# HeadAmp1_trace1.net
KiCad netlist of a schematic drawn in EAGLE
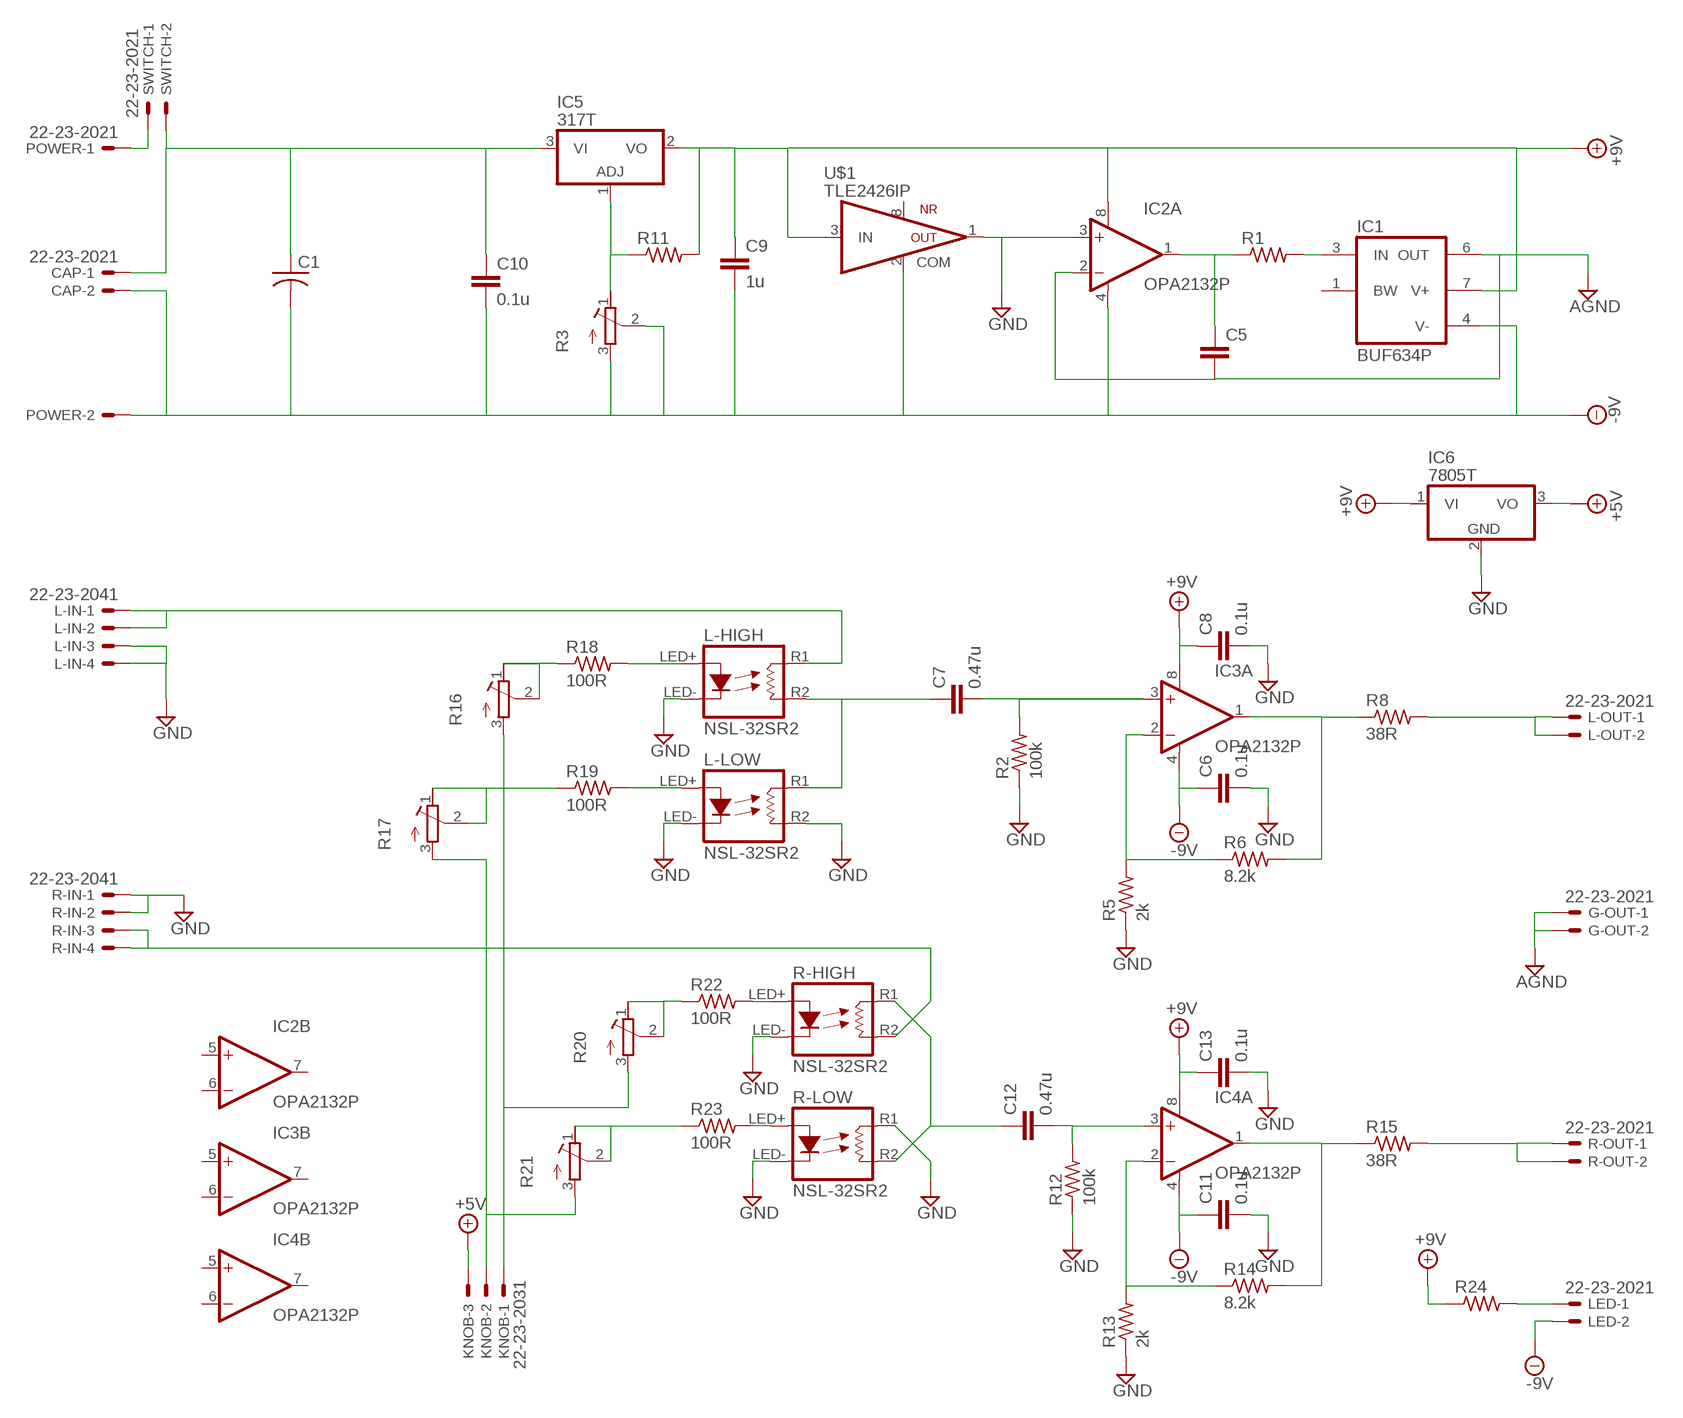
[diagram p0: schematic, sheet 1]

(export (version "E")
  (design (tool "Eeschema 10.0.6"))
  (components
    (comp (ref "C1")
      (value "C-US050-075X075")
      (footprint "eagle-import:C050-075X075")
      (libsource (lib "eagle-import") (part "C-US050-075X075"))
    )
    (comp (ref "C5")
      (value "C5/3")
      (footprint "eagle-import:C5B3")
      (libsource (lib "eagle-import") (part "C5/3"))
    )
    (comp (ref "C6")
      (value "0.1u")
      (footprint "eagle-import:C5B3")
      (libsource (lib "eagle-import") (part "C5/3"))
    )
    (comp (ref "C7")
      (value "0.47u")
      (footprint "eagle-import:C5B3")
      (libsource (lib "eagle-import") (part "C5/3"))
    )
    (comp (ref "C8")
      (value "0.1u")
      (footprint "eagle-import:C5B3")
      (libsource (lib "eagle-import") (part "C5/3"))
    )
    (comp (ref "C9")
      (value "1u")
      (footprint "eagle-import:C5B3")
      (libsource (lib "eagle-import") (part "C5/3"))
    )
    (comp (ref "C10")
      (value "0.1u")
      (footprint "eagle-import:C5B3")
      (libsource (lib "eagle-import") (part "C5/3"))
    )
    (comp (ref "C11")
      (value "0.1u")
      (footprint "eagle-import:C5B3")
      (libsource (lib "eagle-import") (part "C5/3"))
    )
    (comp (ref "C12")
      (value "0.47u")
      (footprint "eagle-import:C5B3")
      (libsource (lib "eagle-import") (part "C5/3"))
    )
    (comp (ref "C13")
      (value "0.1u")
      (footprint "eagle-import:C5B3")
      (libsource (lib "eagle-import") (part "C5/3"))
    )
    (comp (ref "CAP")
      (value "22-23-2021")
      (footprint "eagle-import:22-23-2021")
      (fields (field (name "MF") "MOLEX"))
      (libsource (lib "eagle-import") (part "22-23-2021"))
    )
    (comp (ref "G-OUT")
      (value "22-23-2021")
      (footprint "eagle-import:22-23-2021")
      (fields (field (name "MF") "MOLEX"))
      (libsource (lib "eagle-import") (part "22-23-2021"))
    )
    (comp (ref "IC1")
      (value "BUF634P")
      (footprint "eagle-import:DIL08")
      (fields (field (name "MF") "TEXAS INSTRUMENTS"))
      (libsource (lib "eagle-import") (part "BUF634P"))
    )
    (comp (ref "IC2")
      (value "OPA2132P")
      (footprint "eagle-import:DIL08")
      (libsource (lib "eagle-import") (part "OPA2132P"))
    )
    (comp (ref "IC3")
      (value "OPA2132P")
      (footprint "eagle-import:DIL08")
      (libsource (lib "eagle-import") (part "OPA2132P"))
    )
    (comp (ref "IC4")
      (value "OPA2132P")
      (footprint "eagle-import:DIL08")
      (libsource (lib "eagle-import") (part "OPA2132P"))
    )
    (comp (ref "IC5")
      (value "317T")
      (footprint "eagle-import:TO220H")
      (libsource (lib "eagle-import") (part "317T"))
    )
    (comp (ref "IC6")
      (value "7805T")
      (footprint "eagle-import:TO220H")
      (libsource (lib "eagle-import") (part "78T05"))
    )
    (comp (ref "KNOB")
      (value "22-23-2031")
      (footprint "eagle-import:22-23-2031")
      (fields (field (name "MF") "MOLEX"))
      (libsource (lib "eagle-import") (part "22-23-2031"))
    )
    (comp (ref "L-HIGH")
      (value "NSL-32SR2")
      (footprint "eagle-import:OPTO_32SR")
      (libsource (lib "eagle-import") (part "NSL-32SR2"))
    )
    (comp (ref "L-IN")
      (value "22-23-2041")
      (footprint "eagle-import:22-23-2041")
      (fields (field (name "MF") "MOLEX"))
      (libsource (lib "eagle-import") (part "22-23-2041"))
    )
    (comp (ref "L-LOW")
      (value "NSL-32SR2")
      (footprint "eagle-import:OPTO_32SR")
      (libsource (lib "eagle-import") (part "NSL-32SR2"))
    )
    (comp (ref "L-OUT")
      (value "22-23-2021")
      (footprint "eagle-import:22-23-2021")
      (fields (field (name "MF") "MOLEX"))
      (libsource (lib "eagle-import") (part "22-23-2021"))
    )
    (comp (ref "LED")
      (value "22-23-2021")
      (footprint "eagle-import:22-23-2021")
      (fields (field (name "MF") "MOLEX"))
      (libsource (lib "eagle-import") (part "22-23-2021"))
    )
    (comp (ref "POWER")
      (value "22-23-2021")
      (footprint "eagle-import:22-23-2021")
      (fields (field (name "MF") "MOLEX"))
      (libsource (lib "eagle-import") (part "22-23-2021"))
    )
    (comp (ref "R-HIGH")
      (value "NSL-32SR2")
      (footprint "eagle-import:OPTO_32SR")
      (libsource (lib "eagle-import") (part "NSL-32SR2"))
    )
    (comp (ref "R-IN")
      (value "22-23-2041")
      (footprint "eagle-import:22-23-2041")
      (fields (field (name "MF") "MOLEX"))
      (libsource (lib "eagle-import") (part "22-23-2041"))
    )
    (comp (ref "R-LOW")
      (value "NSL-32SR2")
      (footprint "eagle-import:OPTO_32SR")
      (libsource (lib "eagle-import") (part "NSL-32SR2"))
    )
    (comp (ref "R-OUT")
      (value "22-23-2021")
      (footprint "eagle-import:22-23-2021")
      (fields (field (name "MF") "MOLEX"))
      (libsource (lib "eagle-import") (part "22-23-2021"))
    )
    (comp (ref "R1")
      (value "R-US_0207/10")
      (footprint "eagle-import:0207_10")
      (libsource (lib "eagle-import") (part "R-US_0207/10"))
    )
    (comp (ref "R2")
      (value "100k")
      (footprint "eagle-import:0207_10")
      (libsource (lib "eagle-import") (part "R-US_0207/10"))
    )
    (comp (ref "R3")
      (value "R-TRIMMT93YB")
      (footprint "eagle-import:RTRIMT93YB")
      (libsource (lib "eagle-import") (part "R-TRIMMT93YB"))
    )
    (comp (ref "R5")
      (value "2k")
      (footprint "eagle-import:0207_10")
      (libsource (lib "eagle-import") (part "R-US_0207/10"))
    )
    (comp (ref "R6")
      (value "8.2k")
      (footprint "eagle-import:0207_10")
      (libsource (lib "eagle-import") (part "R-US_0207/10"))
    )
    (comp (ref "R8")
      (value "38R")
      (footprint "eagle-import:0207_10")
      (libsource (lib "eagle-import") (part "R-US_0207/10"))
    )
    (comp (ref "R11")
      (value "R-US_0207/10")
      (footprint "eagle-import:0207_10")
      (libsource (lib "eagle-import") (part "R-US_0207/10"))
    )
    (comp (ref "R12")
      (value "100k")
      (footprint "eagle-import:0207_10")
      (libsource (lib "eagle-import") (part "R-US_0207/10"))
    )
    (comp (ref "R13")
      (value "2k")
      (footprint "eagle-import:0207_10")
      (libsource (lib "eagle-import") (part "R-US_0207/10"))
    )
    (comp (ref "R14")
      (value "8.2k")
      (footprint "eagle-import:0207_10")
      (libsource (lib "eagle-import") (part "R-US_0207/10"))
    )
    (comp (ref "R15")
      (value "38R")
      (footprint "eagle-import:0207_10")
      (libsource (lib "eagle-import") (part "R-US_0207/10"))
    )
    (comp (ref "R16")
      (value "R-TRIMMT93YB")
      (footprint "eagle-import:RTRIMT93YB")
      (libsource (lib "eagle-import") (part "R-TRIMMT93YB"))
    )
    (comp (ref "R17")
      (value "R-TRIMMT93YB")
      (footprint "eagle-import:RTRIMT93YB")
      (libsource (lib "eagle-import") (part "R-TRIMMT93YB"))
    )
    (comp (ref "R18")
      (value "100R")
      (footprint "eagle-import:0207_10")
      (libsource (lib "eagle-import") (part "R-US_0207/10"))
    )
    (comp (ref "R19")
      (value "100R")
      (footprint "eagle-import:0207_10")
      (libsource (lib "eagle-import") (part "R-US_0207/10"))
    )
    (comp (ref "R20")
      (value "R-TRIMMT93YB")
      (footprint "eagle-import:RTRIMT93YB")
      (libsource (lib "eagle-import") (part "R-TRIMMT93YB"))
    )
    (comp (ref "R21")
      (value "R-TRIMMT93YB")
      (footprint "eagle-import:RTRIMT93YB")
      (libsource (lib "eagle-import") (part "R-TRIMMT93YB"))
    )
    (comp (ref "R22")
      (value "100R")
      (footprint "eagle-import:0207_10")
      (libsource (lib "eagle-import") (part "R-US_0207/10"))
    )
    (comp (ref "R23")
      (value "100R")
      (footprint "eagle-import:0207_10")
      (libsource (lib "eagle-import") (part "R-US_0207/10"))
    )
    (comp (ref "R24")
      (value "R-US_0207/10")
      (footprint "eagle-import:0207_10")
      (libsource (lib "eagle-import") (part "R-US_0207/10"))
    )
    (comp (ref "SWITCH")
      (value "22-23-2021")
      (footprint "eagle-import:22-23-2021")
      (fields (field (name "MF") "MOLEX"))
      (libsource (lib "eagle-import") (part "22-23-2021"))
    )
    (comp (ref "U$1")
      (value "TLE2426IP")
      (footprint "eagle-import:DIL08")
      (libsource (lib "eagle-import") (part "TLE2426IP"))
    )
  )
  (nets
    (net (code "1") (name "+5V") (class "Default")
      (node (ref "IC6") (pin "3") (pinfunction "VO_3") (pintype "passive"))
      (node (ref "KNOB") (pin "3") (pinfunction "S_3") (pintype "passive"))
    )
    (net (code "2") (name "+9V") (class "Default")
      (node (ref "C13") (pin "1") (pinfunction "1_1") (pintype "passive"))
      (node (ref "C8") (pin "1") (pinfunction "1_1") (pintype "passive"))
      (node (ref "C9") (pin "1") (pinfunction "1_1") (pintype "passive"))
      (node (ref "IC1") (pin "7") (pinfunction "V+_7") (pintype "power_in"))
      (node (ref "IC2") (pin "8") (pinfunction "V+_8") (pintype "power_in"))
      (node (ref "IC3") (pin "8") (pinfunction "V+_8") (pintype "power_in"))
      (node (ref "IC4") (pin "8") (pinfunction "V+_8") (pintype "power_in"))
      (node (ref "IC5") (pin "2") (pinfunction "VO_2") (pintype "passive"))
      (node (ref "IC6") (pin "1") (pinfunction "VI_1") (pintype "input"))
      (node (ref "R11") (pin "2") (pinfunction "2_2") (pintype "passive"))
      (node (ref "R24") (pin "1") (pinfunction "1_1") (pintype "passive"))
      (node (ref "U$1") (pin "3") (pinfunction "IN_3") (pintype "input"))
    )
    (net (code "3") (name "-9V") (class "Default")
      (node (ref "C1") (pin "2") (pinfunction "2_2") (pintype "passive"))
      (node (ref "C10") (pin "2") (pinfunction "2_2") (pintype "passive"))
      (node (ref "C11") (pin "1") (pinfunction "1_1") (pintype "passive"))
      (node (ref "C6") (pin "1") (pinfunction "1_1") (pintype "passive"))
      (node (ref "C9") (pin "2") (pinfunction "2_2") (pintype "passive"))
      (node (ref "CAP") (pin "2") (pinfunction "S_2") (pintype "passive"))
      (node (ref "IC1") (pin "4") (pinfunction "V-_4") (pintype "power_in"))
      (node (ref "IC2") (pin "4") (pinfunction "V-_4") (pintype "power_in"))
      (node (ref "IC3") (pin "4") (pinfunction "V-_4") (pintype "power_in"))
      (node (ref "IC4") (pin "4") (pinfunction "V-_4") (pintype "power_in"))
      (node (ref "LED") (pin "2") (pinfunction "S_2") (pintype "passive"))
      (node (ref "POWER") (pin "2") (pinfunction "S_2") (pintype "passive"))
      (node (ref "R3") (pin "2") (pinfunction "S_2") (pintype "passive"))
      (node (ref "R3") (pin "3") (pinfunction "E_3") (pintype "passive"))
      (node (ref "U$1") (pin "2") (pinfunction "COMMON_2") (pintype "passive"))
    )
    (net (code "4") (name "AGND") (class "Default")
      (node (ref "C5") (pin "2") (pinfunction "2_2") (pintype "passive"))
      (node (ref "G-OUT") (pin "1") (pinfunction "S_1") (pintype "passive"))
      (node (ref "G-OUT") (pin "2") (pinfunction "S_2") (pintype "passive"))
      (node (ref "IC1") (pin "6") (pinfunction "OUT_6") (pintype "output"))
      (node (ref "IC2") (pin "2") (pinfunction "-IN_2") (pintype "input"))
    )
    (net (code "5") (name "GND") (class "Default")
      (node (ref "C11") (pin "2") (pinfunction "2_2") (pintype "passive"))
      (node (ref "C13") (pin "2") (pinfunction "2_2") (pintype "passive"))
      (node (ref "C6") (pin "2") (pinfunction "2_2") (pintype "passive"))
      (node (ref "C8") (pin "2") (pinfunction "2_2") (pintype "passive"))
      (node (ref "IC2") (pin "3") (pinfunction "+IN_3") (pintype "input"))
      (node (ref "IC6") (pin "2") (pinfunction "GND_2") (pintype "passive"))
      (node (ref "L-HIGH") (pin "LED-") (pinfunction "C_LED-") (pintype "passive"))
      (node (ref "L-IN") (pin "3") (pinfunction "S_3") (pintype "passive"))
      (node (ref "L-IN") (pin "4") (pinfunction "S_4") (pintype "passive"))
      (node (ref "L-LOW") (pin "LED-") (pinfunction "C_LED-") (pintype "passive"))
      (node (ref "L-LOW") (pin "R2") (pinfunction "L2_R2") (pintype "passive"))
      (node (ref "R-HIGH") (pin "LED-") (pinfunction "C_LED-") (pintype "passive"))
      (node (ref "R-IN") (pin "1") (pinfunction "S_1") (pintype "passive"))
      (node (ref "R-IN") (pin "2") (pinfunction "S_2") (pintype "passive"))
      (node (ref "R-LOW") (pin "LED-") (pinfunction "C_LED-") (pintype "passive"))
      (node (ref "R-LOW") (pin "R1") (pinfunction "L1_R1") (pintype "passive"))
      (node (ref "R12") (pin "1") (pinfunction "1_1") (pintype "passive"))
      (node (ref "R13") (pin "1") (pinfunction "1_1") (pintype "passive"))
      (node (ref "R2") (pin "1") (pinfunction "1_1") (pintype "passive"))
      (node (ref "R5") (pin "1") (pinfunction "1_1") (pintype "passive"))
      (node (ref "U$1") (pin "1") (pinfunction "OUT_1") (pintype "passive"))
    )
    (net (code "6") (name "Net-(CAPA-S)") (class "Default")
      (node (ref "C1") (pin "1") (pinfunction "1_1") (pintype "passive"))
      (node (ref "C10") (pin "1") (pinfunction "1_1") (pintype "passive"))
      (node (ref "CAP") (pin "1") (pinfunction "S_1") (pintype "passive"))
      (node (ref "IC5") (pin "3") (pinfunction "VI_3") (pintype "input"))
      (node (ref "SWITCH") (pin "2") (pinfunction "S_2") (pintype "passive"))
    )
    (net (code "7") (name "Net-(IC1-IN)") (class "Default")
      (node (ref "IC1") (pin "3") (pinfunction "IN_3") (pintype "input"))
      (node (ref "R1") (pin "2") (pinfunction "2_2") (pintype "passive"))
    )
    (net (code "8") (name "Net-(IC2A-OUT)") (class "Default")
      (node (ref "C5") (pin "1") (pinfunction "1_1") (pintype "passive"))
      (node (ref "IC2") (pin "1") (pinfunction "OUT_1") (pintype "output"))
      (node (ref "R1") (pin "1") (pinfunction "1_1") (pintype "passive"))
    )
    (net (code "9") (name "Net-(IC3A-+IN)") (class "Default")
      (node (ref "C7") (pin "2") (pinfunction "2_2") (pintype "passive"))
      (node (ref "IC3") (pin "3") (pinfunction "+IN_3") (pintype "input"))
      (node (ref "R2") (pin "2") (pinfunction "2_2") (pintype "passive"))
    )
    (net (code "10") (name "Net-(IC3A--IN)") (class "Default")
      (node (ref "IC3") (pin "2") (pinfunction "-IN_2") (pintype "input"))
      (node (ref "R5") (pin "2") (pinfunction "2_2") (pintype "passive"))
      (node (ref "R6") (pin "1") (pinfunction "1_1") (pintype "passive"))
    )
    (net (code "11") (name "Net-(IC3A-OUT)") (class "Default")
      (node (ref "IC3") (pin "1") (pinfunction "OUT_1") (pintype "output"))
      (node (ref "R6") (pin "2") (pinfunction "2_2") (pintype "passive"))
      (node (ref "R8") (pin "1") (pinfunction "1_1") (pintype "passive"))
    )
    (net (code "12") (name "Net-(IC4A-+IN)") (class "Default")
      (node (ref "C12") (pin "2") (pinfunction "2_2") (pintype "passive"))
      (node (ref "IC4") (pin "3") (pinfunction "+IN_3") (pintype "input"))
      (node (ref "R12") (pin "2") (pinfunction "2_2") (pintype "passive"))
    )
    (net (code "13") (name "Net-(IC4A--IN)") (class "Default")
      (node (ref "IC4") (pin "2") (pinfunction "-IN_2") (pintype "input"))
      (node (ref "R13") (pin "2") (pinfunction "2_2") (pintype "passive"))
      (node (ref "R14") (pin "1") (pinfunction "1_1") (pintype "passive"))
    )
    (net (code "14") (name "Net-(IC4A-OUT)") (class "Default")
      (node (ref "IC4") (pin "1") (pinfunction "OUT_1") (pintype "output"))
      (node (ref "R14") (pin "2") (pinfunction "2_2") (pintype "passive"))
      (node (ref "R15") (pin "1") (pinfunction "1_1") (pintype "passive"))
    )
    (net (code "15") (name "Net-(IC5-ADJ)") (class "Default")
      (node (ref "IC5") (pin "1") (pinfunction "ADJ_1") (pintype "input"))
      (node (ref "R11") (pin "1") (pinfunction "1_1") (pintype "passive"))
      (node (ref "R3") (pin "1") (pinfunction "A_1") (pintype "passive"))
    )
    (net (code "16") (name "Net-(KNOBA-S)") (class "Default")
      (node (ref "KNOB") (pin "1") (pinfunction "S_1") (pintype "passive"))
      (node (ref "R16") (pin "3") (pinfunction "E_3") (pintype "passive"))
      (node (ref "R20") (pin "3") (pinfunction "E_3") (pintype "passive"))
    )
    (net (code "17") (name "Net-(KNOBB-S)") (class "Default")
      (node (ref "KNOB") (pin "2") (pinfunction "S_2") (pintype "passive"))
      (node (ref "R17") (pin "3") (pinfunction "E_3") (pintype "passive"))
      (node (ref "R21") (pin "3") (pinfunction "E_3") (pintype "passive"))
    )
    (net (code "18") (name "Net-(L-HIGH-A)") (class "Default")
      (node (ref "L-HIGH") (pin "LED+") (pinfunction "A_LED+") (pintype "passive"))
      (node (ref "R18") (pin "2") (pinfunction "2_2") (pintype "passive"))
    )
    (net (code "19") (name "Net-(L-HIGH-L1)") (class "Default")
      (node (ref "L-HIGH") (pin "R1") (pinfunction "L1_R1") (pintype "passive"))
      (node (ref "L-IN") (pin "1") (pinfunction "S_1") (pintype "passive"))
      (node (ref "L-IN") (pin "2") (pinfunction "S_2") (pintype "passive"))
    )
    (net (code "20") (name "Net-(L-HIGH-L2)") (class "Default")
      (node (ref "C7") (pin "1") (pinfunction "1_1") (pintype "passive"))
      (node (ref "L-HIGH") (pin "R2") (pinfunction "L2_R2") (pintype "passive"))
      (node (ref "L-LOW") (pin "R1") (pinfunction "L1_R1") (pintype "passive"))
    )
    (net (code "21") (name "Net-(L-LOW-A)") (class "Default")
      (node (ref "L-LOW") (pin "LED+") (pinfunction "A_LED+") (pintype "passive"))
      (node (ref "R19") (pin "2") (pinfunction "2_2") (pintype "passive"))
    )
    (net (code "22") (name "Net-(L-OUTA-S)") (class "Default")
      (node (ref "L-OUT") (pin "1") (pinfunction "S_1") (pintype "passive"))
      (node (ref "L-OUT") (pin "2") (pinfunction "S_2") (pintype "passive"))
      (node (ref "R8") (pin "2") (pinfunction "2_2") (pintype "passive"))
    )
    (net (code "23") (name "Net-(LEDA-S)") (class "Default")
      (node (ref "LED") (pin "1") (pinfunction "S_1") (pintype "passive"))
      (node (ref "R24") (pin "2") (pinfunction "2_2") (pintype "passive"))
    )
    (net (code "24") (name "Net-(POWERA-S)") (class "Default")
      (node (ref "POWER") (pin "1") (pinfunction "S_1") (pintype "passive"))
      (node (ref "SWITCH") (pin "1") (pinfunction "S_1") (pintype "passive"))
    )
    (net (code "25") (name "Net-(R-HIGH-A)") (class "Default")
      (node (ref "R-HIGH") (pin "LED+") (pinfunction "A_LED+") (pintype "passive"))
      (node (ref "R22") (pin "2") (pinfunction "2_2") (pintype "passive"))
    )
    (net (code "26") (name "Net-(R-HIGH-L1)") (class "Default")
      (node (ref "C12") (pin "1") (pinfunction "1_1") (pintype "passive"))
      (node (ref "R-HIGH") (pin "R1") (pinfunction "L1_R1") (pintype "passive"))
      (node (ref "R-LOW") (pin "R2") (pinfunction "L2_R2") (pintype "passive"))
    )
    (net (code "27") (name "Net-(R-HIGH-L2)") (class "Default")
      (node (ref "R-HIGH") (pin "R2") (pinfunction "L2_R2") (pintype "passive"))
      (node (ref "R-IN") (pin "3") (pinfunction "S_3") (pintype "passive"))
      (node (ref "R-IN") (pin "4") (pinfunction "S_4") (pintype "passive"))
    )
    (net (code "28") (name "Net-(R-LOW-A)") (class "Default")
      (node (ref "R-LOW") (pin "LED+") (pinfunction "A_LED+") (pintype "passive"))
      (node (ref "R23") (pin "2") (pinfunction "2_2") (pintype "passive"))
    )
    (net (code "29") (name "Net-(R-OUTA-S)") (class "Default")
      (node (ref "R-OUT") (pin "1") (pinfunction "S_1") (pintype "passive"))
      (node (ref "R-OUT") (pin "2") (pinfunction "S_2") (pintype "passive"))
      (node (ref "R15") (pin "2") (pinfunction "2_2") (pintype "passive"))
    )
    (net (code "30") (name "Net-(R16-A)") (class "Default")
      (node (ref "R16") (pin "1") (pinfunction "A_1") (pintype "passive"))
      (node (ref "R16") (pin "2") (pinfunction "S_2") (pintype "passive"))
      (node (ref "R18") (pin "1") (pinfunction "1_1") (pintype "passive"))
    )
    (net (code "31") (name "Net-(R17-A)") (class "Default")
      (node (ref "R17") (pin "1") (pinfunction "A_1") (pintype "passive"))
      (node (ref "R17") (pin "2") (pinfunction "S_2") (pintype "passive"))
      (node (ref "R19") (pin "1") (pinfunction "1_1") (pintype "passive"))
    )
    (net (code "32") (name "Net-(R20-A)") (class "Default")
      (node (ref "R20") (pin "1") (pinfunction "A_1") (pintype "passive"))
      (node (ref "R20") (pin "2") (pinfunction "S_2") (pintype "passive"))
      (node (ref "R22") (pin "1") (pinfunction "1_1") (pintype "passive"))
    )
    (net (code "33") (name "Net-(R21-A)") (class "Default")
      (node (ref "R21") (pin "1") (pinfunction "A_1") (pintype "passive"))
      (node (ref "R21") (pin "2") (pinfunction "S_2") (pintype "passive"))
      (node (ref "R23") (pin "1") (pinfunction "1_1") (pintype "passive"))
    )
    (net (code "34") (name "unconnected-(IC1-BW-Pad1)") (class "Default")
      (node (ref "IC1") (pin "1") (pinfunction "BW_1") (pintype "passive"))
    )
    (net (code "35") (name "unconnected-(IC2B-+IN-Pad5)") (class "Default")
      (node (ref "IC2") (pin "5") (pinfunction "+IN_5") (pintype "input"))
    )
    (net (code "36") (name "unconnected-(IC2B--IN-Pad6)") (class "Default")
      (node (ref "IC2") (pin "6") (pinfunction "-IN_6") (pintype "input"))
    )
    (net (code "37") (name "unconnected-(IC2B-OUT-Pad7)") (class "Default")
      (node (ref "IC2") (pin "7") (pinfunction "OUT_7") (pintype "output"))
    )
    (net (code "38") (name "unconnected-(IC3B-+IN-Pad5)") (class "Default")
      (node (ref "IC3") (pin "5") (pinfunction "+IN_5") (pintype "input"))
    )
    (net (code "39") (name "unconnected-(IC3B--IN-Pad6)") (class "Default")
      (node (ref "IC3") (pin "6") (pinfunction "-IN_6") (pintype "input"))
    )
    (net (code "40") (name "unconnected-(IC3B-OUT-Pad7)") (class "Default")
      (node (ref "IC3") (pin "7") (pinfunction "OUT_7") (pintype "output"))
    )
    (net (code "41") (name "unconnected-(IC4B-+IN-Pad5)") (class "Default")
      (node (ref "IC4") (pin "5") (pinfunction "+IN_5") (pintype "input"))
    )
    (net (code "42") (name "unconnected-(IC4B--IN-Pad6)") (class "Default")
      (node (ref "IC4") (pin "6") (pinfunction "-IN_6") (pintype "input"))
    )
    (net (code "43") (name "unconnected-(IC4B-OUT-Pad7)") (class "Default")
      (node (ref "IC4") (pin "7") (pinfunction "OUT_7") (pintype "output"))
    )
    (net (code "44") (name "unconnected-(U$1-NR-Pad8)") (class "Default")
      (node (ref "U$1") (pin "8") (pinfunction "NR_8") (pintype "bidirectional"))
    )
  )
)
